# shield.net
KiCad netlist of a schematic drawn in EAGLE
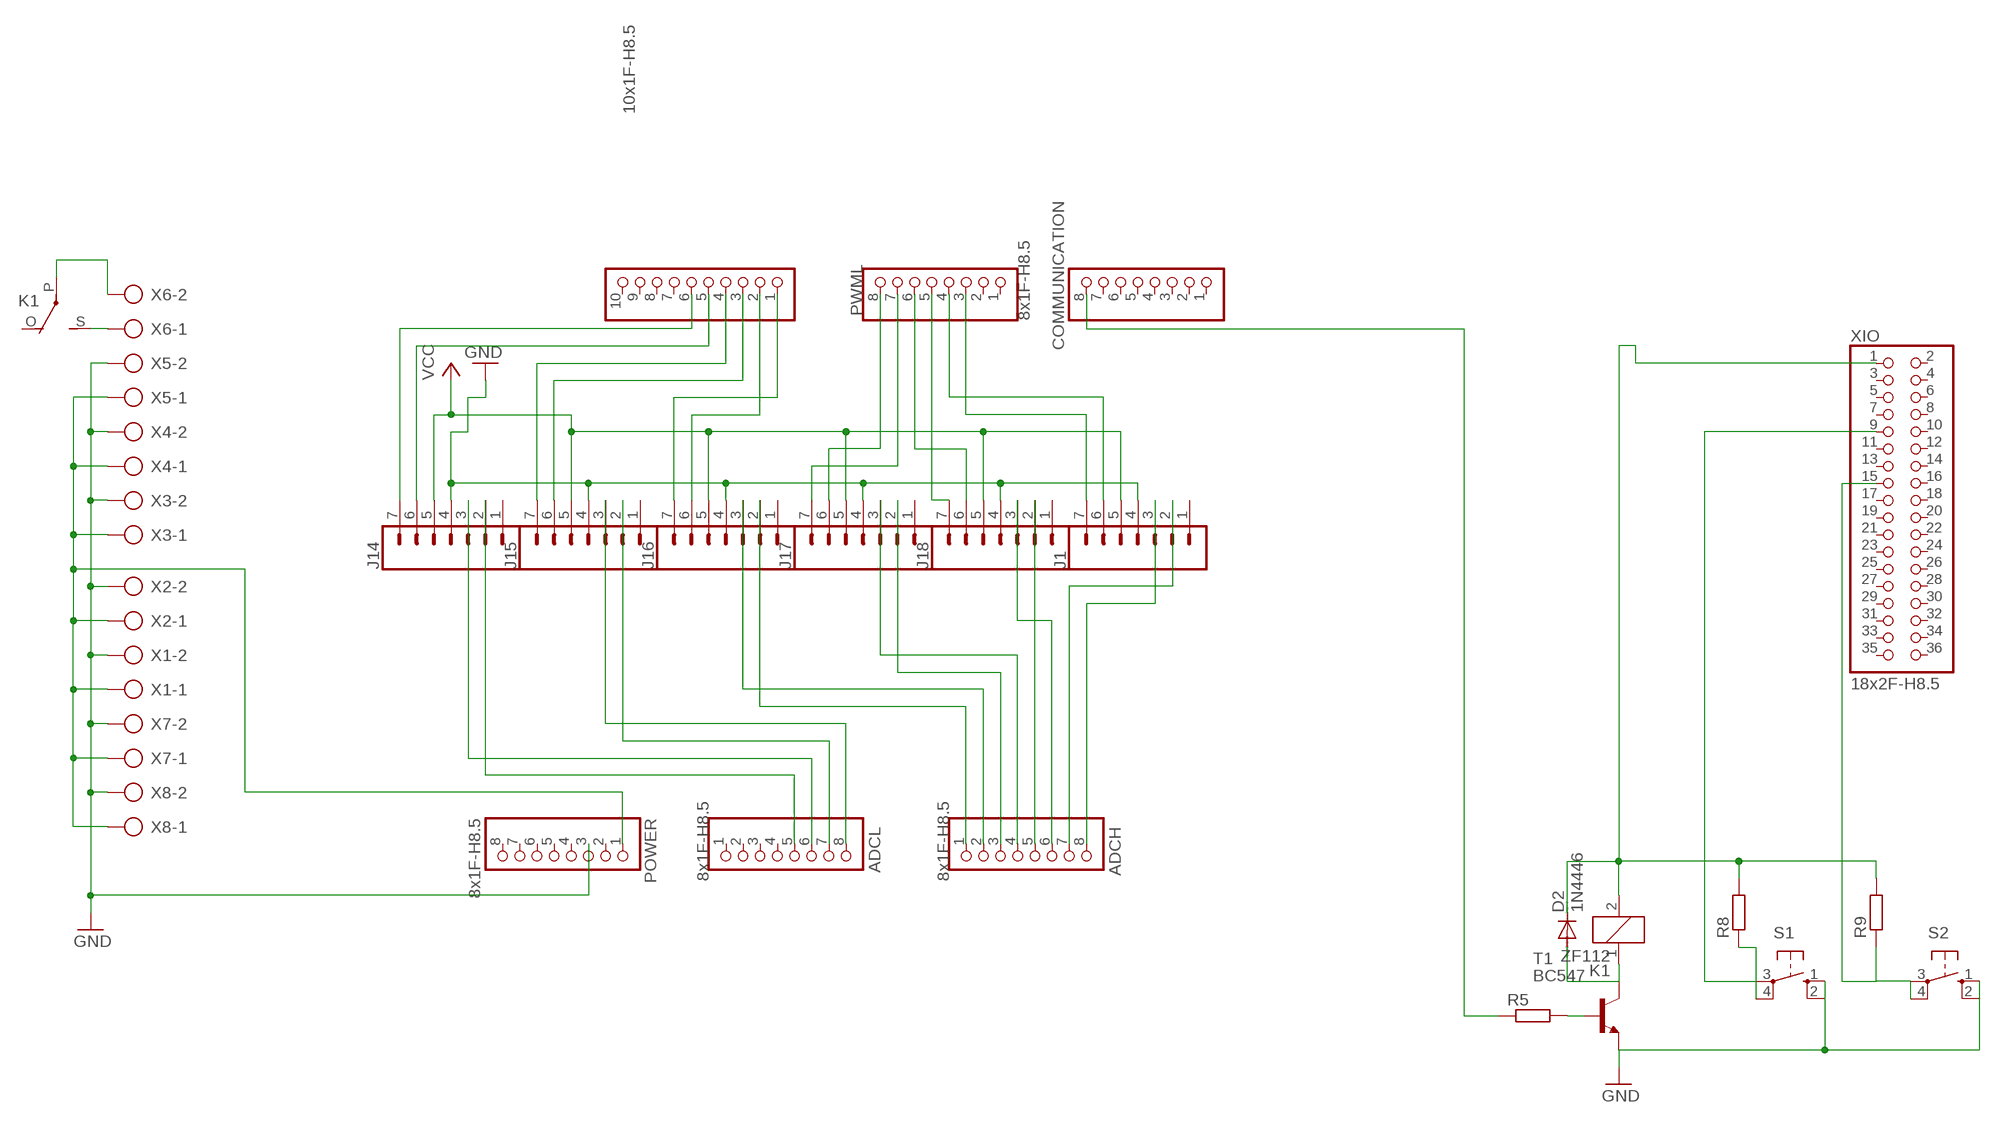
[diagram p0: schematic, sheet 1]

(export (version "E")
  (design (tool "Eeschema 10.0.6"))
  (components
    (comp (ref "ADCH")
      (value "8x1F-H8.5")
      (footprint "eagle-import:1X08")
      (libsource (lib "eagle-import") (part "PINHD-1X8"))
    )
    (comp (ref "ADCL")
      (value "8x1F-H8.5")
      (footprint "eagle-import:1X08")
      (libsource (lib "eagle-import") (part "PINHD-1X8"))
    )
    (comp (ref "COMMUNICATION")
      (value "8x1F-H8.5")
      (footprint "eagle-import:1X08")
      (libsource (lib "eagle-import") (part "PINHD-1X8"))
    )
    (comp (ref "D2")
      (value "1N4446")
      (footprint "eagle-import:DO35-10")
      (libsource (lib "eagle-import") (part "1N4446"))
    )
    (comp (ref "J1")
      (value "CONN_07LONGPADS")
      (footprint "eagle-import:1X07_LONGPADS")
      (libsource (lib "eagle-import") (part "CONN_07LONGPADS"))
    )
    (comp (ref "J14")
      (value "CONN_07LONGPADS")
      (footprint "eagle-import:1X07_LONGPADS")
      (libsource (lib "eagle-import") (part "CONN_07LONGPADS"))
    )
    (comp (ref "J15")
      (value "CONN_07LONGPADS")
      (footprint "eagle-import:1X07_LONGPADS")
      (libsource (lib "eagle-import") (part "CONN_07LONGPADS"))
    )
    (comp (ref "J16")
      (value "CONN_07LONGPADS")
      (footprint "eagle-import:1X07_LONGPADS")
      (libsource (lib "eagle-import") (part "CONN_07LONGPADS"))
    )
    (comp (ref "J17")
      (value "CONN_07LONGPADS")
      (footprint "eagle-import:1X07_LONGPADS")
      (libsource (lib "eagle-import") (part "CONN_07LONGPADS"))
    )
    (comp (ref "J18")
      (value "CONN_07LONGPADS")
      (footprint "eagle-import:1X07_LONGPADS")
      (libsource (lib "eagle-import") (part "CONN_07LONGPADS"))
    )
    (comp (ref "K1")
      (value "ZF112")
      (footprint "eagle-import:ZF112")
      (libsource (lib "eagle-import") (part "ZF112"))
    )
    (comp (ref "POWER")
      (value "8x1F-H8.5")
      (footprint "eagle-import:1X08")
      (libsource (lib "eagle-import") (part "PINHD-1X8"))
    )
    (comp (ref "PWMH")
      (value "10x1F-H8.5")
      (footprint "eagle-import:1X10")
      (libsource (lib "eagle-import") (part "PINHD-1X10"))
    )
    (comp (ref "PWML")
      (value "8x1F-H8.5")
      (footprint "eagle-import:1X08")
      (libsource (lib "eagle-import") (part "PINHD-1X8"))
    )
    (comp (ref "R5")
      (value "R-EU_0204/7")
      (footprint "eagle-import:0204_7")
      (libsource (lib "eagle-import") (part "R-EU_0204/7"))
    )
    (comp (ref "R8")
      (value "R-EU_0204/7")
      (footprint "eagle-import:0204_7")
      (libsource (lib "eagle-import") (part "R-EU_0204/7"))
    )
    (comp (ref "R9")
      (value "R-EU_0204/7")
      (footprint "eagle-import:0204_7")
      (libsource (lib "eagle-import") (part "R-EU_0204/7"))
    )
    (comp (ref "S1")
      (value "10-XX")
      (footprint "eagle-import:B3F-10XX")
      (fields (field (name "MPN") "B3F-1000"))
      (libsource (lib "eagle-import") (part "10-XX"))
    )
    (comp (ref "S2")
      (value "10-XX")
      (footprint "eagle-import:B3F-10XX")
      (fields (field (name "MPN") "B3F-1000"))
      (libsource (lib "eagle-import") (part "10-XX"))
    )
    (comp (ref "T1")
      (value "BC547")
      (footprint "eagle-import:TO92")
      (libsource (lib "eagle-import") (part "BC547"))
    )
    (comp (ref "X1")
      (value "AK500/2")
      (footprint "eagle-import:AK500_2")
      (libsource (lib "eagle-import") (part "AK500/2"))
    )
    (comp (ref "X2")
      (value "AK500/2")
      (footprint "eagle-import:AK500_2")
      (libsource (lib "eagle-import") (part "AK500/2"))
    )
    (comp (ref "X3")
      (value "AK500/2")
      (footprint "eagle-import:AK500_2")
      (libsource (lib "eagle-import") (part "AK500/2"))
    )
    (comp (ref "X4")
      (value "AK500/2")
      (footprint "eagle-import:AK500_2")
      (libsource (lib "eagle-import") (part "AK500/2"))
    )
    (comp (ref "X5")
      (value "AK500/2")
      (footprint "eagle-import:AK500_2")
      (libsource (lib "eagle-import") (part "AK500/2"))
    )
    (comp (ref "X6")
      (value "AK500/2")
      (footprint "eagle-import:AK500_2")
      (libsource (lib "eagle-import") (part "AK500/2"))
    )
    (comp (ref "X7")
      (value "AK500/2")
      (footprint "eagle-import:AK500_2")
      (libsource (lib "eagle-import") (part "AK500/2"))
    )
    (comp (ref "X8")
      (value "AK500/2")
      (footprint "eagle-import:AK500_2")
      (libsource (lib "eagle-import") (part "AK500/2"))
    )
    (comp (ref "XIO")
      (value "18x2F-H8.5")
      (footprint "eagle-import:2X18")
      (libsource (lib "eagle-import") (part "PINHD-2X18"))
    )
  )
  (nets
    (net (code "1") (name "GND") (class "Default")
      (node (ref "J1") (pin "4") (pinfunction "4_4") (pintype "passive"))
      (node (ref "J14") (pin "4") (pinfunction "4_4") (pintype "passive"))
      (node (ref "J15") (pin "4") (pinfunction "4_4") (pintype "passive"))
      (node (ref "J16") (pin "4") (pinfunction "4_4") (pintype "passive"))
      (node (ref "J17") (pin "4") (pinfunction "4_4") (pintype "passive"))
      (node (ref "J18") (pin "4") (pinfunction "4_4") (pintype "passive"))
      (node (ref "POWER") (pin "3") (pinfunction "3_3") (pintype "passive"))
      (node (ref "S1") (pin "1") (pinfunction "S_1") (pintype "passive"))
      (node (ref "S1") (pin "2") (pinfunction "S1_2") (pintype "passive"))
      (node (ref "S2") (pin "1") (pinfunction "S_1") (pintype "passive"))
      (node (ref "S2") (pin "2") (pinfunction "S1_2") (pintype "passive"))
      (node (ref "T1") (pin "1") (pinfunction "E_1") (pintype "passive"))
      (node (ref "X1") (pin "2") (pinfunction "KL_2") (pintype "passive"))
      (node (ref "X2") (pin "2") (pinfunction "KL_2") (pintype "passive"))
      (node (ref "X3") (pin "2") (pinfunction "KL_2") (pintype "passive"))
      (node (ref "X4") (pin "2") (pinfunction "KL_2") (pintype "passive"))
      (node (ref "X5") (pin "2") (pinfunction "KL_2") (pintype "passive"))
      (node (ref "X7") (pin "2") (pinfunction "KL_2") (pintype "passive"))
      (node (ref "X8") (pin "2") (pinfunction "KL_2") (pintype "passive"))
    )
    (net (code "2") (name "Net-(ADCH-Pad1)") (class "Default")
      (node (ref "ADCH") (pin "1") (pinfunction "1_1") (pintype "passive"))
      (node (ref "J16") (pin "2") (pinfunction "2_2") (pintype "passive"))
    )
    (net (code "3") (name "Net-(ADCH-Pad2)") (class "Default")
      (node (ref "ADCH") (pin "2") (pinfunction "2_2") (pintype "passive"))
      (node (ref "J16") (pin "3") (pinfunction "3_3") (pintype "passive"))
    )
    (net (code "4") (name "Net-(ADCH-Pad3)") (class "Default")
      (node (ref "ADCH") (pin "3") (pinfunction "3_3") (pintype "passive"))
      (node (ref "J17") (pin "2") (pinfunction "2_2") (pintype "passive"))
    )
    (net (code "5") (name "Net-(ADCH-Pad4)") (class "Default")
      (node (ref "ADCH") (pin "4") (pinfunction "4_4") (pintype "passive"))
      (node (ref "J17") (pin "3") (pinfunction "3_3") (pintype "passive"))
    )
    (net (code "6") (name "Net-(ADCH-Pad5)") (class "Default")
      (node (ref "ADCH") (pin "5") (pinfunction "5_5") (pintype "passive"))
      (node (ref "J18") (pin "2") (pinfunction "2_2") (pintype "passive"))
    )
    (net (code "7") (name "Net-(ADCH-Pad6)") (class "Default")
      (node (ref "ADCH") (pin "6") (pinfunction "6_6") (pintype "passive"))
      (node (ref "J18") (pin "3") (pinfunction "3_3") (pintype "passive"))
    )
    (net (code "8") (name "Net-(ADCH-Pad7)") (class "Default")
      (node (ref "ADCH") (pin "7") (pinfunction "7_7") (pintype "passive"))
      (node (ref "J1") (pin "2") (pinfunction "2_2") (pintype "passive"))
    )
    (net (code "9") (name "Net-(ADCH-Pad8)") (class "Default")
      (node (ref "ADCH") (pin "8") (pinfunction "8_8") (pintype "passive"))
      (node (ref "J1") (pin "3") (pinfunction "3_3") (pintype "passive"))
    )
    (net (code "10") (name "Net-(ADCL-Pad5)") (class "Default")
      (node (ref "ADCL") (pin "5") (pinfunction "5_5") (pintype "passive"))
      (node (ref "J14") (pin "2") (pinfunction "2_2") (pintype "passive"))
    )
    (net (code "11") (name "Net-(ADCL-Pad6)") (class "Default")
      (node (ref "ADCL") (pin "6") (pinfunction "6_6") (pintype "passive"))
      (node (ref "J14") (pin "3") (pinfunction "3_3") (pintype "passive"))
    )
    (net (code "12") (name "Net-(ADCL-Pad7)") (class "Default")
      (node (ref "ADCL") (pin "7") (pinfunction "7_7") (pintype "passive"))
      (node (ref "J15") (pin "2") (pinfunction "2_2") (pintype "passive"))
    )
    (net (code "13") (name "Net-(ADCL-Pad8)") (class "Default")
      (node (ref "ADCL") (pin "8") (pinfunction "8_8") (pintype "passive"))
      (node (ref "J15") (pin "3") (pinfunction "3_3") (pintype "passive"))
    )
    (net (code "14") (name "Net-(COMMUNICATION-Pad8)") (class "Default")
      (node (ref "COMMUNICATION") (pin "8") (pinfunction "8_8") (pintype "passive"))
      (node (ref "R5") (pin "1") (pinfunction "1_1") (pintype "passive"))
    )
    (net (code "15") (name "Net-(D2-PadC)") (class "Default")
      (node (ref "D2") (pin "C") (pinfunction "C_C") (pintype "passive"))
      (node (ref "K1") (pin "2") (pinfunction "2_2") (pintype "passive"))
      (node (ref "R8") (pin "2") (pinfunction "2_2") (pintype "passive"))
      (node (ref "R9") (pin "2") (pinfunction "2_2") (pintype "passive"))
      (node (ref "XIO") (pin "1") (pinfunction "1_1") (pintype "passive"))
    )
    (net (code "16") (name "Net-(J1-Pad6)") (class "Default")
      (node (ref "J1") (pin "6") (pinfunction "6_6") (pintype "passive"))
      (node (ref "PWML") (pin "4") (pinfunction "4_4") (pintype "passive"))
    )
    (net (code "17") (name "Net-(J1-Pad7)") (class "Default")
      (node (ref "J1") (pin "7") (pinfunction "7_7") (pintype "passive"))
      (node (ref "PWML") (pin "3") (pinfunction "3_3") (pintype "passive"))
    )
    (net (code "18") (name "Net-(J14-Pad6)") (class "Default")
      (node (ref "J14") (pin "6") (pinfunction "6_6") (pintype "passive"))
      (node (ref "PWMH") (pin "5") (pinfunction "5_5") (pintype "passive"))
    )
    (net (code "19") (name "Net-(J14-Pad7)") (class "Default")
      (node (ref "J14") (pin "7") (pinfunction "7_7") (pintype "passive"))
      (node (ref "PWMH") (pin "6") (pinfunction "6_6") (pintype "passive"))
    )
    (net (code "20") (name "Net-(J15-Pad6)") (class "Default")
      (node (ref "J15") (pin "6") (pinfunction "6_6") (pintype "passive"))
      (node (ref "PWMH") (pin "3") (pinfunction "3_3") (pintype "passive"))
    )
    (net (code "21") (name "Net-(J15-Pad7)") (class "Default")
      (node (ref "J15") (pin "7") (pinfunction "7_7") (pintype "passive"))
      (node (ref "PWMH") (pin "4") (pinfunction "4_4") (pintype "passive"))
    )
    (net (code "22") (name "Net-(J16-Pad6)") (class "Default")
      (node (ref "J16") (pin "6") (pinfunction "6_6") (pintype "passive"))
      (node (ref "PWMH") (pin "2") (pinfunction "2_2") (pintype "passive"))
    )
    (net (code "23") (name "Net-(J16-Pad7)") (class "Default")
      (node (ref "J16") (pin "7") (pinfunction "7_7") (pintype "passive"))
      (node (ref "PWMH") (pin "1") (pinfunction "1_1") (pintype "passive"))
    )
    (net (code "24") (name "Net-(J17-Pad6)") (class "Default")
      (node (ref "J17") (pin "6") (pinfunction "6_6") (pintype "passive"))
      (node (ref "PWML") (pin "8") (pinfunction "8_8") (pintype "passive"))
    )
    (net (code "25") (name "Net-(J17-Pad7)") (class "Default")
      (node (ref "J17") (pin "7") (pinfunction "7_7") (pintype "passive"))
      (node (ref "PWML") (pin "7") (pinfunction "7_7") (pintype "passive"))
    )
    (net (code "26") (name "Net-(J18-Pad6)") (class "Default")
      (node (ref "J18") (pin "6") (pinfunction "6_6") (pintype "passive"))
      (node (ref "PWML") (pin "6") (pinfunction "6_6") (pintype "passive"))
    )
    (net (code "27") (name "Net-(J18-Pad7)") (class "Default")
      (node (ref "J18") (pin "7") (pinfunction "7_7") (pintype "passive"))
      (node (ref "PWML") (pin "5") (pinfunction "5_5") (pintype "passive"))
    )
    (net (code "28") (name "Net-(S1-P)") (class "Default")
      (node (ref "R8") (pin "1") (pinfunction "1_1") (pintype "passive"))
      (node (ref "S1") (pin "3") (pinfunction "P_3") (pintype "passive"))
      (node (ref "S1") (pin "4") (pinfunction "P1_4") (pintype "passive"))
      (node (ref "XIO") (pin "9") (pinfunction "9_9") (pintype "passive"))
    )
    (net (code "29") (name "Net-(S2-P)") (class "Default")
      (node (ref "R9") (pin "1") (pinfunction "1_1") (pintype "passive"))
      (node (ref "S2") (pin "3") (pinfunction "P_3") (pintype "passive"))
      (node (ref "S2") (pin "4") (pinfunction "P1_4") (pintype "passive"))
      (node (ref "XIO") (pin "15") (pinfunction "15_15") (pintype "passive"))
    )
    (net (code "30") (name "Net-(T1-B)") (class "Default")
      (node (ref "R5") (pin "2") (pinfunction "2_2") (pintype "passive"))
      (node (ref "T1") (pin "2") (pinfunction "B_2") (pintype "passive"))
    )
    (net (code "31") (name "Net-(T1-C)") (class "Default")
      (node (ref "D2") (pin "A") (pinfunction "A_A") (pintype "passive"))
      (node (ref "K1") (pin "1") (pinfunction "1_1") (pintype "passive"))
      (node (ref "T1") (pin "3") (pinfunction "C_3") (pintype "passive"))
    )
    (net (code "32") (name "Net-(X1A-KL)") (class "Default")
      (node (ref "POWER") (pin "1") (pinfunction "1_1") (pintype "passive"))
      (node (ref "X1") (pin "1") (pinfunction "KL_1") (pintype "passive"))
      (node (ref "X2") (pin "1") (pinfunction "KL_1") (pintype "passive"))
      (node (ref "X3") (pin "1") (pinfunction "KL_1") (pintype "passive"))
      (node (ref "X4") (pin "1") (pinfunction "KL_1") (pintype "passive"))
      (node (ref "X5") (pin "1") (pinfunction "KL_1") (pintype "passive"))
      (node (ref "X7") (pin "1") (pinfunction "KL_1") (pintype "passive"))
      (node (ref "X8") (pin "1") (pinfunction "KL_1") (pintype "passive"))
    )
    (net (code "33") (name "Net-(X6A-KL)") (class "Default")
      (node (ref "K1") (pin "S") (pinfunction "S_S") (pintype "passive"))
      (node (ref "X6") (pin "1") (pinfunction "KL_1") (pintype "passive"))
    )
    (net (code "34") (name "Net-(X6B-KL)") (class "Default")
      (node (ref "K1") (pin "P") (pinfunction "P_P") (pintype "passive"))
      (node (ref "X6") (pin "2") (pinfunction "KL_2") (pintype "passive"))
    )
    (net (code "35") (name "VCC") (class "Default")
      (node (ref "J1") (pin "5") (pinfunction "5_5") (pintype "passive"))
      (node (ref "J14") (pin "5") (pinfunction "5_5") (pintype "passive"))
      (node (ref "J15") (pin "5") (pinfunction "5_5") (pintype "passive"))
      (node (ref "J16") (pin "5") (pinfunction "5_5") (pintype "passive"))
      (node (ref "J17") (pin "5") (pinfunction "5_5") (pintype "passive"))
      (node (ref "J18") (pin "5") (pinfunction "5_5") (pintype "passive"))
    )
    (net (code "36") (name "unconnected-(ADCL-Pad1)") (class "Default")
      (node (ref "ADCL") (pin "1") (pinfunction "1_1") (pintype "passive"))
    )
    (net (code "37") (name "unconnected-(ADCL-Pad2)") (class "Default")
      (node (ref "ADCL") (pin "2") (pinfunction "2_2") (pintype "passive"))
    )
    (net (code "38") (name "unconnected-(ADCL-Pad3)") (class "Default")
      (node (ref "ADCL") (pin "3") (pinfunction "3_3") (pintype "passive"))
    )
    (net (code "39") (name "unconnected-(ADCL-Pad4)") (class "Default")
      (node (ref "ADCL") (pin "4") (pinfunction "4_4") (pintype "passive"))
    )
    (net (code "40") (name "unconnected-(COMMUNICATION-Pad1)") (class "Default")
      (node (ref "COMMUNICATION") (pin "1") (pinfunction "1_1") (pintype "passive"))
    )
    (net (code "41") (name "unconnected-(COMMUNICATION-Pad2)") (class "Default")
      (node (ref "COMMUNICATION") (pin "2") (pinfunction "2_2") (pintype "passive"))
    )
    (net (code "42") (name "unconnected-(COMMUNICATION-Pad3)") (class "Default")
      (node (ref "COMMUNICATION") (pin "3") (pinfunction "3_3") (pintype "passive"))
    )
    (net (code "43") (name "unconnected-(COMMUNICATION-Pad4)") (class "Default")
      (node (ref "COMMUNICATION") (pin "4") (pinfunction "4_4") (pintype "passive"))
    )
    (net (code "44") (name "unconnected-(COMMUNICATION-Pad5)") (class "Default")
      (node (ref "COMMUNICATION") (pin "5") (pinfunction "5_5") (pintype "passive"))
    )
    (net (code "45") (name "unconnected-(COMMUNICATION-Pad6)") (class "Default")
      (node (ref "COMMUNICATION") (pin "6") (pinfunction "6_6") (pintype "passive"))
    )
    (net (code "46") (name "unconnected-(COMMUNICATION-Pad7)") (class "Default")
      (node (ref "COMMUNICATION") (pin "7") (pinfunction "7_7") (pintype "passive"))
    )
    (net (code "47") (name "unconnected-(J1-Pad1)") (class "Default")
      (node (ref "J1") (pin "1") (pinfunction "1_1") (pintype "passive"))
    )
    (net (code "48") (name "unconnected-(J14-Pad1)") (class "Default")
      (node (ref "J14") (pin "1") (pinfunction "1_1") (pintype "passive"))
    )
    (net (code "49") (name "unconnected-(J15-Pad1)") (class "Default")
      (node (ref "J15") (pin "1") (pinfunction "1_1") (pintype "passive"))
    )
    (net (code "50") (name "unconnected-(J16-Pad1)") (class "Default")
      (node (ref "J16") (pin "1") (pinfunction "1_1") (pintype "passive"))
    )
    (net (code "51") (name "unconnected-(J17-Pad1)") (class "Default")
      (node (ref "J17") (pin "1") (pinfunction "1_1") (pintype "passive"))
    )
    (net (code "52") (name "unconnected-(J18-Pad1)") (class "Default")
      (node (ref "J18") (pin "1") (pinfunction "1_1") (pintype "passive"))
    )
    (net (code "53") (name "unconnected-(K1-PadO)") (class "Default")
      (node (ref "K1") (pin "O") (pinfunction "O_O") (pintype "passive"))
    )
    (net (code "54") (name "unconnected-(POWER-Pad2)") (class "Default")
      (node (ref "POWER") (pin "2") (pinfunction "2_2") (pintype "passive"))
    )
    (net (code "55") (name "unconnected-(POWER-Pad4)") (class "Default")
      (node (ref "POWER") (pin "4") (pinfunction "4_4") (pintype "passive"))
    )
    (net (code "56") (name "unconnected-(POWER-Pad5)") (class "Default")
      (node (ref "POWER") (pin "5") (pinfunction "5_5") (pintype "passive"))
    )
    (net (code "57") (name "unconnected-(POWER-Pad6)") (class "Default")
      (node (ref "POWER") (pin "6") (pinfunction "6_6") (pintype "passive"))
    )
    (net (code "58") (name "unconnected-(POWER-Pad7)") (class "Default")
      (node (ref "POWER") (pin "7") (pinfunction "7_7") (pintype "passive"))
    )
    (net (code "59") (name "unconnected-(POWER-Pad8)") (class "Default")
      (node (ref "POWER") (pin "8") (pinfunction "8_8") (pintype "passive"))
    )
    (net (code "60") (name "unconnected-(PWMH-Pad7)") (class "Default")
      (node (ref "PWMH") (pin "7") (pinfunction "7_7") (pintype "passive"))
    )
    (net (code "61") (name "unconnected-(PWMH-Pad8)") (class "Default")
      (node (ref "PWMH") (pin "8") (pinfunction "8_8") (pintype "passive"))
    )
    (net (code "62") (name "unconnected-(PWMH-Pad9)") (class "Default")
      (node (ref "PWMH") (pin "9") (pinfunction "9_9") (pintype "passive"))
    )
    (net (code "63") (name "unconnected-(PWMH-Pad10)") (class "Default")
      (node (ref "PWMH") (pin "10") (pinfunction "10_10") (pintype "passive"))
    )
    (net (code "64") (name "unconnected-(PWML-Pad1)") (class "Default")
      (node (ref "PWML") (pin "1") (pinfunction "1_1") (pintype "passive"))
    )
    (net (code "65") (name "unconnected-(PWML-Pad2)") (class "Default")
      (node (ref "PWML") (pin "2") (pinfunction "2_2") (pintype "passive"))
    )
    (net (code "66") (name "unconnected-(XIO-Pad2)") (class "Default")
      (node (ref "XIO") (pin "2") (pinfunction "2_2") (pintype "passive"))
    )
    (net (code "67") (name "unconnected-(XIO-Pad3)") (class "Default")
      (node (ref "XIO") (pin "3") (pinfunction "3_3") (pintype "passive"))
    )
    (net (code "68") (name "unconnected-(XIO-Pad4)") (class "Default")
      (node (ref "XIO") (pin "4") (pinfunction "4_4") (pintype "passive"))
    )
    (net (code "69") (name "unconnected-(XIO-Pad5)") (class "Default")
      (node (ref "XIO") (pin "5") (pinfunction "5_5") (pintype "passive"))
    )
    (net (code "70") (name "unconnected-(XIO-Pad6)") (class "Default")
      (node (ref "XIO") (pin "6") (pinfunction "6_6") (pintype "passive"))
    )
    (net (code "71") (name "unconnected-(XIO-Pad7)") (class "Default")
      (node (ref "XIO") (pin "7") (pinfunction "7_7") (pintype "passive"))
    )
    (net (code "72") (name "unconnected-(XIO-Pad8)") (class "Default")
      (node (ref "XIO") (pin "8") (pinfunction "8_8") (pintype "passive"))
    )
    (net (code "73") (name "unconnected-(XIO-Pad10)") (class "Default")
      (node (ref "XIO") (pin "10") (pinfunction "10_10") (pintype "passive"))
    )
    (net (code "74") (name "unconnected-(XIO-Pad11)") (class "Default")
      (node (ref "XIO") (pin "11") (pinfunction "11_11") (pintype "passive"))
    )
    (net (code "75") (name "unconnected-(XIO-Pad12)") (class "Default")
      (node (ref "XIO") (pin "12") (pinfunction "12_12") (pintype "passive"))
    )
    (net (code "76") (name "unconnected-(XIO-Pad13)") (class "Default")
      (node (ref "XIO") (pin "13") (pinfunction "13_13") (pintype "passive"))
    )
    (net (code "77") (name "unconnected-(XIO-Pad14)") (class "Default")
      (node (ref "XIO") (pin "14") (pinfunction "14_14") (pintype "passive"))
    )
    (net (code "78") (name "unconnected-(XIO-Pad16)") (class "Default")
      (node (ref "XIO") (pin "16") (pinfunction "16_16") (pintype "passive"))
    )
    (net (code "79") (name "unconnected-(XIO-Pad17)") (class "Default")
      (node (ref "XIO") (pin "17") (pinfunction "17_17") (pintype "passive"))
    )
    (net (code "80") (name "unconnected-(XIO-Pad18)") (class "Default")
      (node (ref "XIO") (pin "18") (pinfunction "18_18") (pintype "passive"))
    )
    (net (code "81") (name "unconnected-(XIO-Pad19)") (class "Default")
      (node (ref "XIO") (pin "19") (pinfunction "19_19") (pintype "passive"))
    )
    (net (code "82") (name "unconnected-(XIO-Pad20)") (class "Default")
      (node (ref "XIO") (pin "20") (pinfunction "20_20") (pintype "passive"))
    )
    (net (code "83") (name "unconnected-(XIO-Pad21)") (class "Default")
      (node (ref "XIO") (pin "21") (pinfunction "21_21") (pintype "passive"))
    )
    (net (code "84") (name "unconnected-(XIO-Pad22)") (class "Default")
      (node (ref "XIO") (pin "22") (pinfunction "22_22") (pintype "passive"))
    )
    (net (code "85") (name "unconnected-(XIO-Pad23)") (class "Default")
      (node (ref "XIO") (pin "23") (pinfunction "23_23") (pintype "passive"))
    )
    (net (code "86") (name "unconnected-(XIO-Pad24)") (class "Default")
      (node (ref "XIO") (pin "24") (pinfunction "24_24") (pintype "passive"))
    )
    (net (code "87") (name "unconnected-(XIO-Pad25)") (class "Default")
      (node (ref "XIO") (pin "25") (pinfunction "25_25") (pintype "passive"))
    )
    (net (code "88") (name "unconnected-(XIO-Pad26)") (class "Default")
      (node (ref "XIO") (pin "26") (pinfunction "26_26") (pintype "passive"))
    )
    (net (code "89") (name "unconnected-(XIO-Pad27)") (class "Default")
      (node (ref "XIO") (pin "27") (pinfunction "27_27") (pintype "passive"))
    )
    (net (code "90") (name "unconnected-(XIO-Pad28)") (class "Default")
      (node (ref "XIO") (pin "28") (pinfunction "28_28") (pintype "passive"))
    )
    (net (code "91") (name "unconnected-(XIO-Pad29)") (class "Default")
      (node (ref "XIO") (pin "29") (pinfunction "29_29") (pintype "passive"))
    )
    (net (code "92") (name "unconnected-(XIO-Pad30)") (class "Default")
      (node (ref "XIO") (pin "30") (pinfunction "30_30") (pintype "passive"))
    )
    (net (code "93") (name "unconnected-(XIO-Pad31)") (class "Default")
      (node (ref "XIO") (pin "31") (pinfunction "31_31") (pintype "passive"))
    )
    (net (code "94") (name "unconnected-(XIO-Pad32)") (class "Default")
      (node (ref "XIO") (pin "32") (pinfunction "32_32") (pintype "passive"))
    )
    (net (code "95") (name "unconnected-(XIO-Pad33)") (class "Default")
      (node (ref "XIO") (pin "33") (pinfunction "33_33") (pintype "passive"))
    )
    (net (code "96") (name "unconnected-(XIO-Pad34)") (class "Default")
      (node (ref "XIO") (pin "34") (pinfunction "34_34") (pintype "passive"))
    )
    (net (code "97") (name "unconnected-(XIO-Pad35)") (class "Default")
      (node (ref "XIO") (pin "35") (pinfunction "35_35") (pintype "passive"))
    )
    (net (code "98") (name "unconnected-(XIO-Pad36)") (class "Default")
      (node (ref "XIO") (pin "36") (pinfunction "36_36") (pintype "passive"))
    )
  )
)
